# Sheet3.net
KiCad netlist of a schematic drawn in Altium Designer
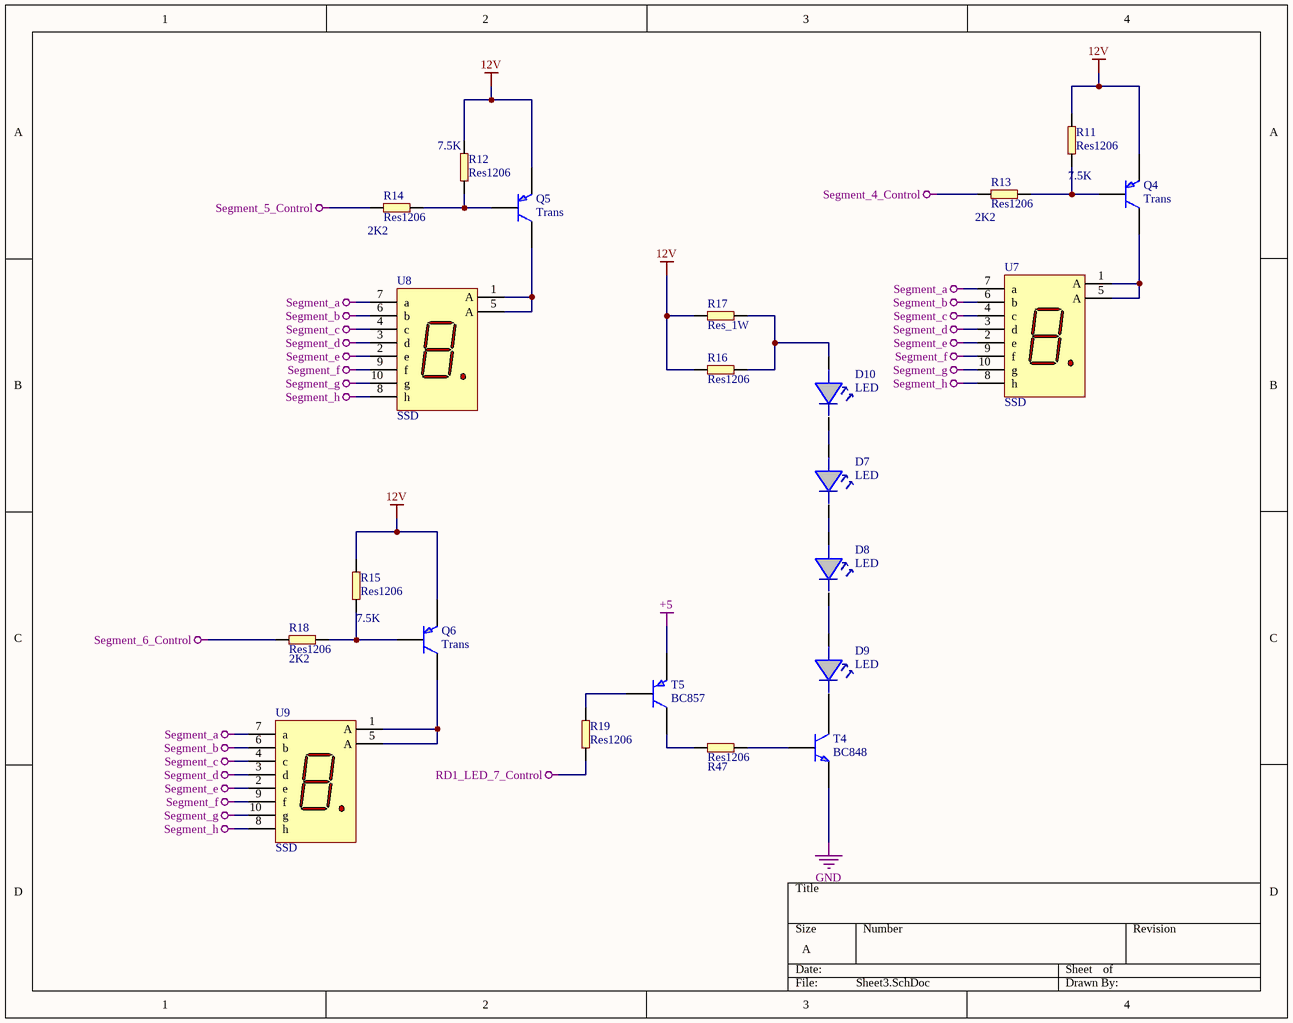
[diagram p0: Sheet3.SchDoc]

(export (version "E")
  (design (tool "Eeschema 10.0.6"))
  (components
    (comp (ref "D7")
      (value "LED")
      (footprint "LED5MM")
      (description "LED_5MM")
      (libsource (lib "Dinesh_New_Integrated_Library") (part "LED_5MM"))
    )
    (comp (ref "D8")
      (value "LED")
      (footprint "LED5MM")
      (description "LED_5MM")
      (libsource (lib "Dinesh_New_Integrated_Library") (part "LED_5MM"))
    )
    (comp (ref "D9")
      (value "LED")
      (footprint "LED5MM")
      (description "LED_5MM")
      (libsource (lib "Dinesh_New_Integrated_Library") (part "LED_5MM"))
    )
    (comp (ref "D10")
      (value "LED")
      (footprint "LED5MM")
      (description "LED_5MM")
      (libsource (lib "Dinesh_New_Integrated_Library") (part "LED_5MM"))
    )
    (comp (ref "Q4")
      (value "Trans")
      (footprint "2N6107")
      (description "pnp transistor")
      (libsource (lib "VIJAYIntegrated_Library") (part "2N6107"))
    )
    (comp (ref "Q5")
      (value "Trans")
      (footprint "2N6107")
      (description "pnp transistor")
      (libsource (lib "VIJAYIntegrated_Library") (part "2N6107"))
    )
    (comp (ref "Q6")
      (value "Trans")
      (footprint "2N6107")
      (description "pnp transistor")
      (libsource (lib "VIJAYIntegrated_Library") (part "2N6107"))
    )
    (comp (ref "R11")
      (value "Res1206")
      (footprint "1206")
      (fields (field (name "ALTIUM_VALUE") "7.5K"))
      (libsource (lib "Dinesh_New_Integrated_Library") (part "Res1206"))
    )
    (comp (ref "R12")
      (value "Res1206")
      (footprint "1206")
      (fields (field (name "ALTIUM_VALUE") "7.5K"))
      (libsource (lib "") (part "Res1206_3"))
    )
    (comp (ref "R13")
      (value "Res1206")
      (footprint "1206")
      (fields (field (name "ALTIUM_VALUE") "2K2"))
      (libsource (lib "") (part "Res1206_2"))
    )
    (comp (ref "R14")
      (value "Res1206")
      (footprint "1206")
      (fields (field (name "ALTIUM_VALUE") "2K2"))
      (libsource (lib "") (part "Res1206_1"))
    )
    (comp (ref "R15")
      (value "Res1206")
      (footprint "1206")
      (fields (field (name "ALTIUM_VALUE") "7.5K"))
      (libsource (lib "Dinesh_New_Integrated_Library") (part "Res1206"))
    )
    (comp (ref "R16") (value "Res1206") (footprint "1206") (libsource (lib "") (part "Res1206_2")))
    (comp (ref "R17")
      (value "Res_1W")
      (footprint "RES_400_1W")
      (libsource (lib "Dinesh_New_Integrated_Library") (part "Res_1W"))
    )
    (comp (ref "R18")
      (value "Res1206")
      (footprint "1206")
      (fields (field (name "ALTIUM_VALUE") "2K2"))
      (libsource (lib "") (part "Res1206_2"))
    )
    (comp (ref "R19") (value "Res1206") (footprint "1206") (libsource (lib "") (part "Res1206_3")))
    (comp (ref "R47") (value "Res1206") (footprint "1206") (libsource (lib "") (part "Res1206_1")))
    (comp (ref "T4")
      (value "BC848")
      (footprint "SOT23")
      (description "TRANSISTOR")
      (libsource (lib "Dinesh_New_Integrated_Library") (part "BC848"))
    )
    (comp (ref "T5")
      (value "BC857")
      (footprint "SOT23")
      (libsource (lib "Dinesh_New_Integrated_Library") (part "BC857"))
    )
    (comp (ref "U7")
      (value "SSD")
      (footprint "SP1802_SSD")
      (description "SSD 48MM")
      (libsource (lib "VIJAYIntegrated_Library") (part "SP1802"))
    )
    (comp (ref "U8")
      (value "SSD")
      (footprint "SP1802_SSD")
      (description "SSD 48MM")
      (libsource (lib "VIJAYIntegrated_Library") (part "SP1802"))
    )
    (comp (ref "U9")
      (value "SSD")
      (footprint "SP1802_SSD")
      (description "SSD 48MM")
      (libsource (lib "VIJAYIntegrated_Library") (part "SP1802"))
    )
  )
  (nets
    (net (code "1") (name "+5") (class "Default")
      (node (ref "T5") (pin "2") (pinfunction "E_2") (pintype "passive"))
    )
    (net (code "2") (name "12V") (class "Default")
      (node (ref "Q4") (pin "3") (pinfunction "E_3") (pintype "passive"))
      (node (ref "Q5") (pin "3") (pinfunction "E_3") (pintype "passive"))
      (node (ref "Q6") (pin "3") (pinfunction "E_3") (pintype "passive"))
      (node (ref "R11") (pin "2") (pinfunction "b_2") (pintype "passive"))
      (node (ref "R12") (pin "1") (pinfunction "a_1") (pintype "passive"))
      (node (ref "R15") (pin "2") (pinfunction "b_2") (pintype "passive"))
      (node (ref "R16") (pin "1") (pinfunction "a_1") (pintype "passive"))
      (node (ref "R17") (pin "2") (pinfunction "b_2") (pintype "passive"))
    )
    (net (code "3") (name "GND") (class "Default")
      (node (ref "T4") (pin "2") (pinfunction "E_2") (pintype "passive"))
    )
    (net (code "4") (name "Net-(D7-B)") (class "Default")
      (node (ref "D7") (pin "2") (pinfunction "B_2") (pintype "passive"))
      (node (ref "D8") (pin "1") (pinfunction "A_1") (pintype "passive"))
    )
    (net (code "5") (name "Net-(D8-B)") (class "Default")
      (node (ref "D8") (pin "2") (pinfunction "B_2") (pintype "passive"))
      (node (ref "D9") (pin "1") (pinfunction "A_1") (pintype "passive"))
    )
    (net (code "6") (name "Net-(D9-B)") (class "Default")
      (node (ref "D9") (pin "2") (pinfunction "B_2") (pintype "passive"))
      (node (ref "T4") (pin "3") (pinfunction "C_3") (pintype "passive"))
    )
    (net (code "7") (name "Net-(D10-A)") (class "Default")
      (node (ref "D10") (pin "1") (pinfunction "A_1") (pintype "passive"))
      (node (ref "R16") (pin "2") (pinfunction "b_2") (pintype "passive"))
      (node (ref "R17") (pin "1") (pinfunction "a_1") (pintype "passive"))
    )
    (net (code "8") (name "Net-(D10-B)") (class "Default")
      (node (ref "D10") (pin "2") (pinfunction "B_2") (pintype "passive"))
      (node (ref "D7") (pin "1") (pinfunction "A_1") (pintype "passive"))
    )
    (net (code "9") (name "Net-(Q4-B)") (class "Default")
      (node (ref "Q4") (pin "1") (pinfunction "B_1") (pintype "passive"))
      (node (ref "R11") (pin "1") (pinfunction "a_1") (pintype "passive"))
      (node (ref "R13") (pin "2") (pinfunction "b_2") (pintype "passive"))
    )
    (net (code "10") (name "Net-(Q4-C)") (class "Default")
      (node (ref "Q4") (pin "2") (pinfunction "C_2") (pintype "passive"))
      (node (ref "U7") (pin "1") (pinfunction "A_1") (pintype "passive"))
      (node (ref "U7") (pin "5") (pinfunction "A_5") (pintype "passive"))
    )
    (net (code "11") (name "Net-(Q5-B)") (class "Default")
      (node (ref "Q5") (pin "1") (pinfunction "B_1") (pintype "passive"))
      (node (ref "R12") (pin "2") (pinfunction "b_2") (pintype "passive"))
      (node (ref "R14") (pin "1") (pinfunction "a_1") (pintype "passive"))
    )
    (net (code "12") (name "Net-(Q5-C)") (class "Default")
      (node (ref "Q5") (pin "2") (pinfunction "C_2") (pintype "passive"))
      (node (ref "U8") (pin "1") (pinfunction "A_1") (pintype "passive"))
      (node (ref "U8") (pin "5") (pinfunction "A_5") (pintype "passive"))
    )
    (net (code "13") (name "Net-(Q6-B)") (class "Default")
      (node (ref "Q6") (pin "1") (pinfunction "B_1") (pintype "passive"))
      (node (ref "R15") (pin "1") (pinfunction "a_1") (pintype "passive"))
      (node (ref "R18") (pin "2") (pinfunction "b_2") (pintype "passive"))
    )
    (net (code "14") (name "Net-(Q6-C)") (class "Default")
      (node (ref "Q6") (pin "2") (pinfunction "C_2") (pintype "passive"))
      (node (ref "U9") (pin "1") (pinfunction "A_1") (pintype "passive"))
      (node (ref "U9") (pin "5") (pinfunction "A_5") (pintype "passive"))
    )
    (net (code "15") (name "Net-(R19-a)") (class "Default")
      (node (ref "R19") (pin "1") (pinfunction "a_1") (pintype "passive"))
      (node (ref "T5") (pin "1") (pinfunction "B_1") (pintype "passive"))
    )
    (net (code "16") (name "Net-(R47-a)") (class "Default")
      (node (ref "R47") (pin "1") (pinfunction "a_1") (pintype "passive"))
      (node (ref "T4") (pin "1") (pinfunction "B_1") (pintype "passive"))
    )
    (net (code "17") (name "Net-(R47-b)") (class "Default")
      (node (ref "R47") (pin "2") (pinfunction "b_2") (pintype "passive"))
      (node (ref "T5") (pin "3") (pinfunction "C_3") (pintype "passive"))
    )
    (net (code "18") (name "RD1_LED_7_Control") (class "Default")
      (node (ref "R19") (pin "2") (pinfunction "b_2") (pintype "passive"))
    )
    (net (code "19") (name "Segment_4_Control") (class "Default")
      (node (ref "R13") (pin "1") (pinfunction "a_1") (pintype "passive"))
    )
    (net (code "20") (name "Segment_5_Control") (class "Default")
      (node (ref "R14") (pin "2") (pinfunction "b_2") (pintype "passive"))
    )
    (net (code "21") (name "Segment_6_Control") (class "Default")
      (node (ref "R18") (pin "1") (pinfunction "a_1") (pintype "passive"))
    )
    (net (code "22") (name "Segment_a") (class "Default")
      (node (ref "U7") (pin "7") (pinfunction "a_7") (pintype "passive"))
      (node (ref "U8") (pin "7") (pinfunction "a_7") (pintype "passive"))
      (node (ref "U9") (pin "7") (pinfunction "a_7") (pintype "passive"))
    )
    (net (code "23") (name "Segment_b") (class "Default")
      (node (ref "U7") (pin "6") (pinfunction "b_6") (pintype "passive"))
      (node (ref "U8") (pin "6") (pinfunction "b_6") (pintype "passive"))
      (node (ref "U9") (pin "6") (pinfunction "b_6") (pintype "passive"))
    )
    (net (code "24") (name "Segment_c") (class "Default")
      (node (ref "U7") (pin "4") (pinfunction "c_4") (pintype "passive"))
      (node (ref "U8") (pin "4") (pinfunction "c_4") (pintype "passive"))
      (node (ref "U9") (pin "4") (pinfunction "c_4") (pintype "passive"))
    )
    (net (code "25") (name "Segment_d") (class "Default")
      (node (ref "U7") (pin "3") (pinfunction "d_3") (pintype "passive"))
      (node (ref "U8") (pin "3") (pinfunction "d_3") (pintype "passive"))
      (node (ref "U9") (pin "3") (pinfunction "d_3") (pintype "passive"))
    )
    (net (code "26") (name "Segment_e") (class "Default")
      (node (ref "U7") (pin "2") (pinfunction "e_2") (pintype "passive"))
      (node (ref "U8") (pin "2") (pinfunction "e_2") (pintype "passive"))
      (node (ref "U9") (pin "2") (pinfunction "e_2") (pintype "passive"))
    )
    (net (code "27") (name "Segment_f") (class "Default")
      (node (ref "U7") (pin "9") (pinfunction "f_9") (pintype "passive"))
      (node (ref "U8") (pin "9") (pinfunction "f_9") (pintype "passive"))
      (node (ref "U9") (pin "9") (pinfunction "f_9") (pintype "passive"))
    )
    (net (code "28") (name "Segment_g") (class "Default")
      (node (ref "U7") (pin "10") (pinfunction "g_10") (pintype "passive"))
      (node (ref "U8") (pin "10") (pinfunction "g_10") (pintype "passive"))
      (node (ref "U9") (pin "10") (pinfunction "g_10") (pintype "passive"))
    )
    (net (code "29") (name "Segment_h") (class "Default")
      (node (ref "U7") (pin "8") (pinfunction "h_8") (pintype "passive"))
      (node (ref "U8") (pin "8") (pinfunction "h_8") (pintype "passive"))
      (node (ref "U9") (pin "8") (pinfunction "h_8") (pintype "passive"))
    )
  )
)
